# PIC32ETH_Ethernet.net
KiCad netlist of a schematic drawn in Altium Designer
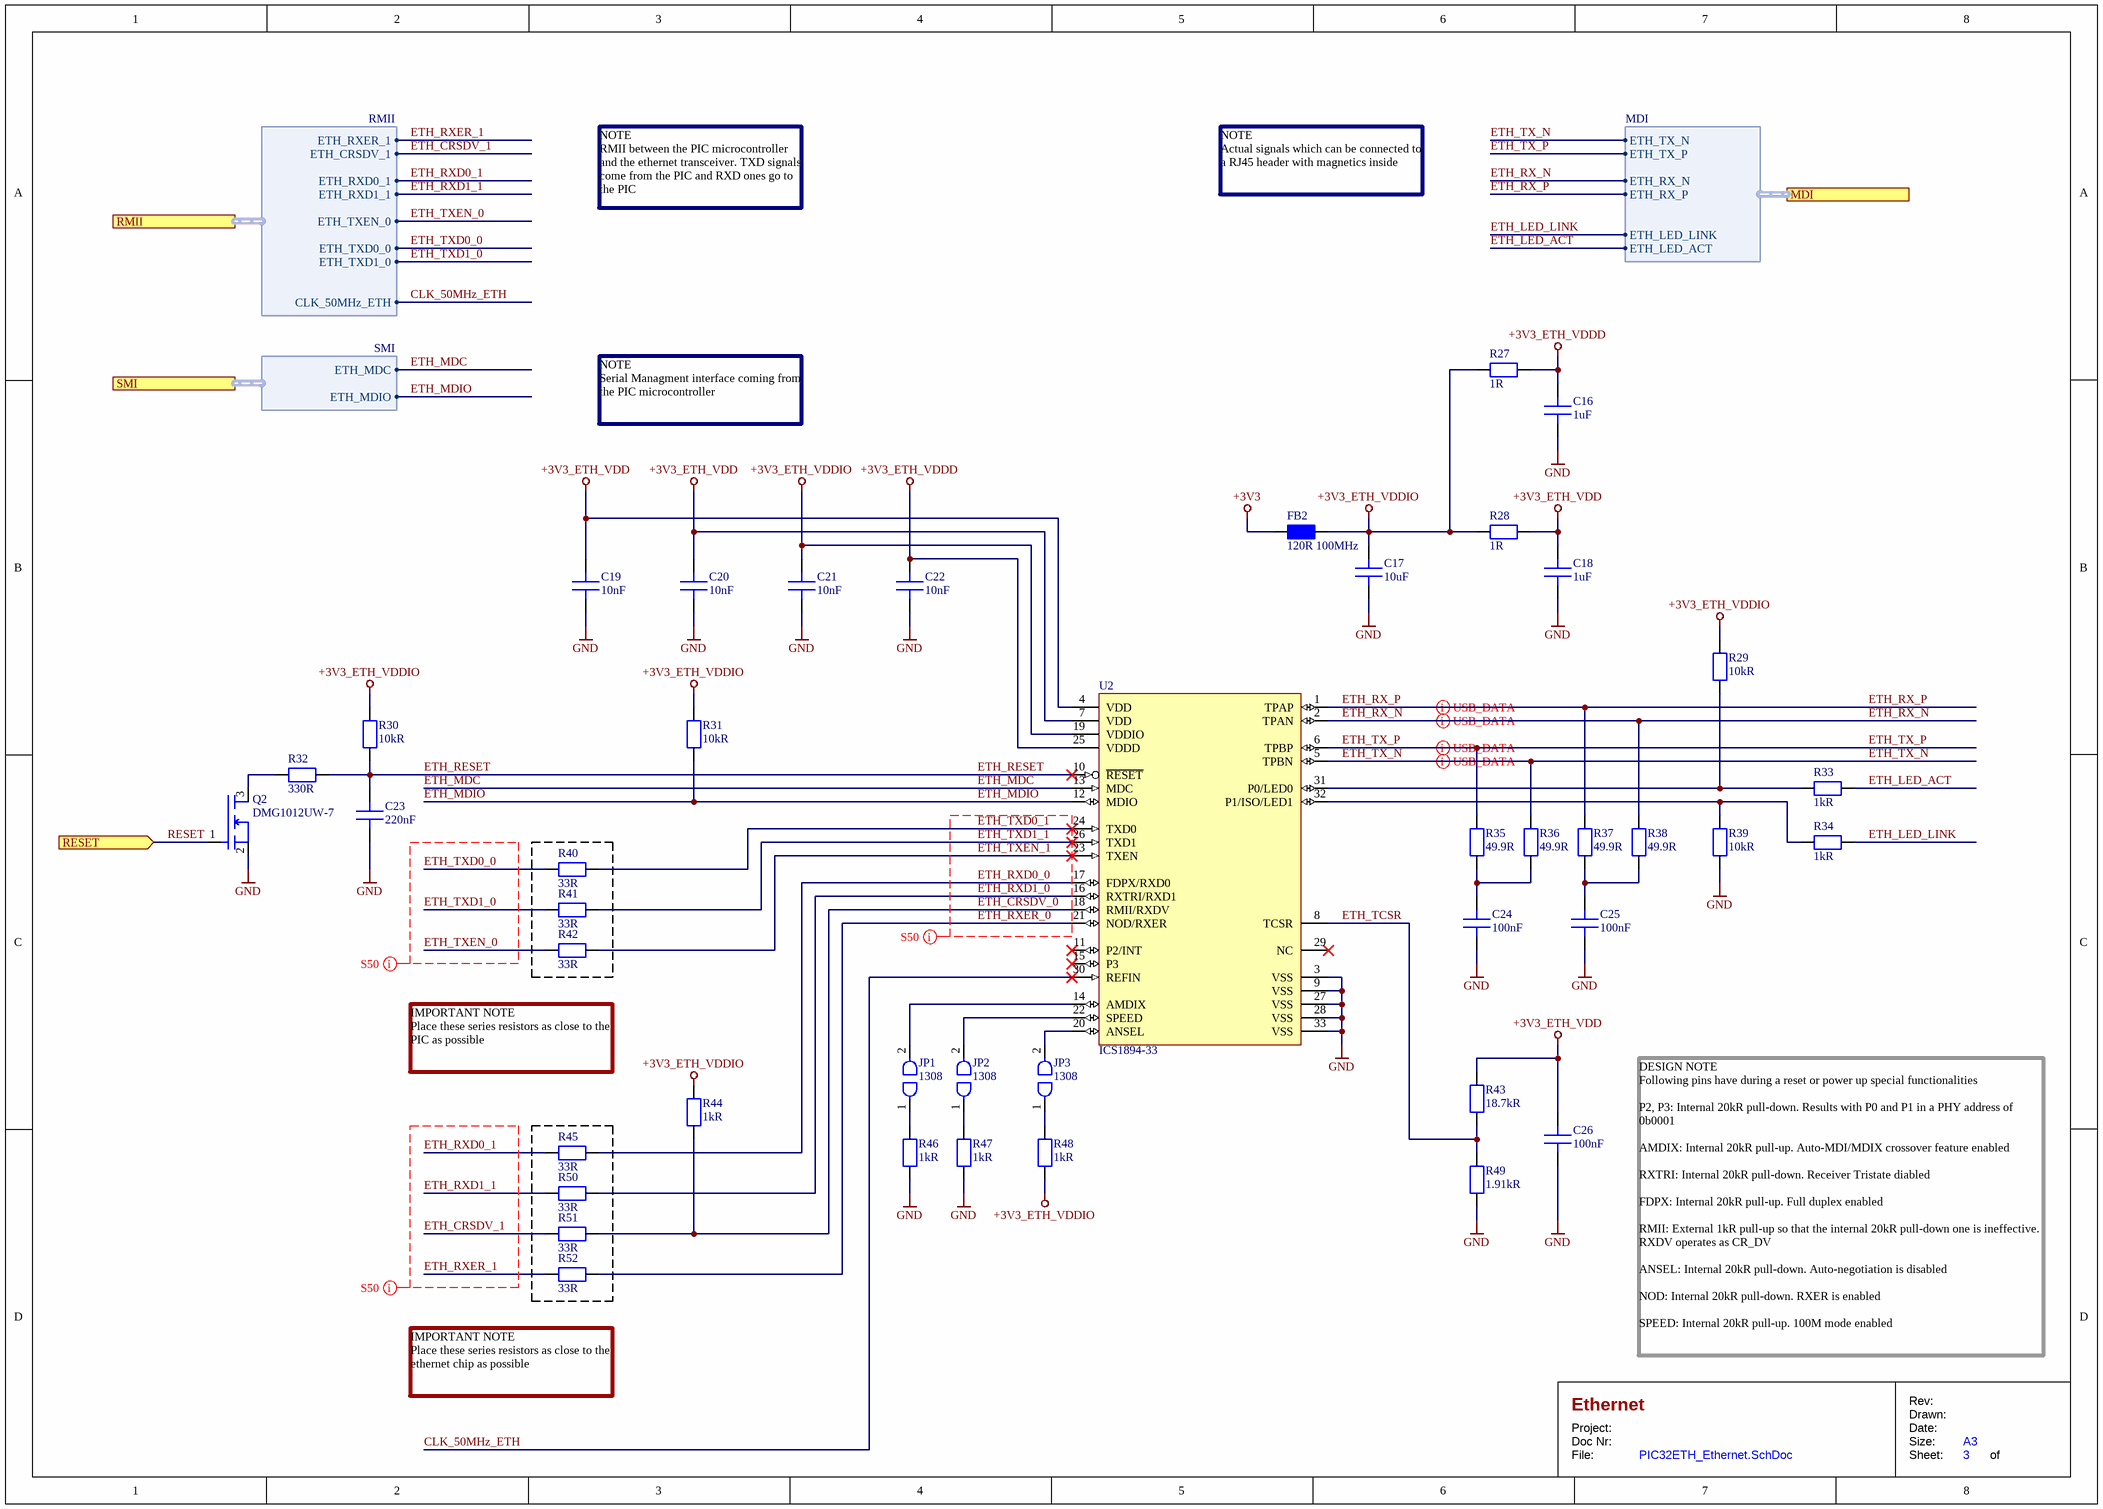
[diagram p0: PIC32ETH_Ethernet.SchDoc]

(export (version "E")
  (design (tool "Eeschema 10.0.6"))
  (components
    (comp (ref "C16")
      (value "1uF")
      (footprint "C_CHIP2012N")
      (description "C CERAMIC 1uF 50V 10% 2012")
      (fields (field (name "MANUFACTURER") "Kemet") (field (name "PART NUMBER") "C0805C105K5RACTU"))
      (libsource (lib "PIC32ETH") (part "C_C0805C105K5RACTU"))
    )
    (comp (ref "C17")
      (value "10uF")
      (footprint "C_CHIP3216N")
      (description "C CERAMIC 10uF 25V 10% 3216")
      (fields (field (name "PART NUMBER") "C1206C106K3RACTU") (field (name "MANUFACTURER") "Kemet"))
      (libsource (lib "PIC32ETH") (part "C_C1206C106K3RACTU"))
    )
    (comp (ref "C18")
      (value "1uF")
      (footprint "C_CHIP2012N")
      (description "C CERAMIC 1uF 50V 10% 2012")
      (fields (field (name "MANUFACTURER") "Kemet") (field (name "PART NUMBER") "C0805C105K5RACTU"))
      (libsource (lib "PIC32ETH") (part "C_C0805C105K5RACTU"))
    )
    (comp (ref "C19")
      (value "10nF")
      (footprint "C_CHIP2012N")
      (description "C CERAMIC 10nF 50V 10% 2012")
      (fields (field (name "MANUFACTURER") "Kemet") (field (name "PART NUMBER") "C0805C103K5RACTU"))
      (libsource (lib "PIC32ETH") (part "C_C0805C103K5RACTU"))
    )
    (comp (ref "C20")
      (value "10nF")
      (footprint "C_CHIP2012N")
      (description "C CERAMIC 10nF 50V 10% 2012")
      (fields (field (name "MANUFACTURER") "Kemet") (field (name "PART NUMBER") "C0805C103K5RACTU"))
      (libsource (lib "PIC32ETH") (part "C_C0805C103K5RACTU"))
    )
    (comp (ref "C21")
      (value "10nF")
      (footprint "C_CHIP2012N")
      (description "C CERAMIC 10nF 50V 10% 2012")
      (fields (field (name "MANUFACTURER") "Kemet") (field (name "PART NUMBER") "C0805C103K5RACTU"))
      (libsource (lib "PIC32ETH") (part "C_C0805C103K5RACTU"))
    )
    (comp (ref "C22")
      (value "10nF")
      (footprint "C_CHIP2012N")
      (description "C CERAMIC 10nF 50V 10% 2012")
      (fields (field (name "MANUFACTURER") "Kemet") (field (name "PART NUMBER") "C0805C103K5RACTU"))
      (libsource (lib "PIC32ETH") (part "C_C0805C103K5RACTU"))
    )
    (comp (ref "C23")
      (value "220nF")
      (footprint "C_CHIP2012N")
      (description "C CERAMIC 220nF 50V 10% 2012")
      (fields (field (name "MANUFACTURER") "Kemet") (field (name "PART NUMBER") "C0805C224K5RACTU"))
      (libsource (lib "PIC32ETH") (part "C_C0805C224K5RACTU"))
    )
    (comp (ref "C24")
      (value "100nF")
      (footprint "C_CHIP2012N")
      (description "C CERAMIC 100nF 50V 10% 2012")
      (fields (field (name "MANUFACTURER") "Kemet") (field (name "PART NUMBER") "C0805C104K5RACTU"))
      (libsource (lib "PIC32ETH") (part "C_C0805C104K5RACTU"))
    )
    (comp (ref "C25")
      (value "100nF")
      (footprint "C_CHIP2012N")
      (description "C CERAMIC 100nF 50V 10% 2012")
      (fields (field (name "MANUFACTURER") "Kemet") (field (name "PART NUMBER") "C0805C104K5RACTU"))
      (libsource (lib "PIC32ETH") (part "C_C0805C104K5RACTU"))
    )
    (comp (ref "C26")
      (value "100nF")
      (footprint "C_CHIP2012N")
      (description "C CERAMIC 100nF 50V 10% 2012")
      (fields (field (name "MANUFACTURER") "Kemet") (field (name "PART NUMBER") "C0805C104K5RACTU"))
      (libsource (lib "PIC32ETH") (part "C_C0805C104K5RACTU"))
    )
    (comp (ref "FB2")
      (value "120R 100MHz")
      (footprint "FB_CHIP3216N")
      (description "FB 120R 100MHz 6A 3216")
      (fields
        (field (name "MANUFACTURER") "Murata Electronics")
        (field (name "PART NUMBER") "BLM31KN121SN1L")
      )
      (libsource (lib "PIC32ETH") (part "FB_BLM31KN121SN1L"))
    )
    (comp (ref "JP1")
      (value "1308")
      (footprint "JP_SOLDER-2POS-1308")
      (description "JP SOLDER 2POS 1308")
      (fields (field (name "MANUFACTURER") "n/a"))
      (libsource (lib "PIC32ETH") (part "JP_SOLDER-2POS-1308"))
    )
    (comp (ref "JP2")
      (value "1308")
      (footprint "JP_SOLDER-2POS-1308")
      (description "JP SOLDER 2POS 1308")
      (fields (field (name "MANUFACTURER") "n/a"))
      (libsource (lib "PIC32ETH") (part "JP_SOLDER-2POS-1308"))
    )
    (comp (ref "JP3")
      (value "1308")
      (footprint "JP_SOLDER-2POS-1308")
      (description "JP SOLDER 2POS 1308")
      (fields (field (name "MANUFACTURER") "n/a"))
      (libsource (lib "PIC32ETH") (part "JP_SOLDER-2POS-1308"))
    )
    (comp (ref "Q2")
      (value "DMG1012UW-7")
      (footprint "Q_SOT65P210X100-3N")
      (description "Q MOSFET N-CH 20V 1A SOT-323")
      (fields (field (name "MANUFACTURER") "Diodes Incorporated") (field (name "POWER") "290mW"))
      (libsource (lib "PIC32ETH") (part "Q_DMG1012UW-7"))
    )
    (comp (ref "R27")
      (value "1R")
      (footprint "R_CHIP2012N")
      (description "R SMT 1R 1% 125mW 2012")
      (fields
        (field (name "MANUFACTURER") "Stackpole Electronics Inc")
        (field (name "PART NUMBER") "RMCF0805FT1R00")
      )
      (libsource (lib "PIC32ETH") (part "R_RMCF0805FT1R00"))
    )
    (comp (ref "R28")
      (value "1R")
      (footprint "R_CHIP2012N")
      (description "R SMT 1R 1% 125mW 2012")
      (fields
        (field (name "MANUFACTURER") "Stackpole Electronics Inc")
        (field (name "PART NUMBER") "RMCF0805FT1R00")
      )
      (libsource (lib "PIC32ETH") (part "R_RMCF0805FT1R00"))
    )
    (comp (ref "R29")
      (value "10kR")
      (footprint "R_CHIP2012N")
      (description "R SMT 10kR 1% 125mW 2012")
      (fields
        (field (name "MANUFACTURER") "Stackpole Electronics Inc")
        (field (name "PART NUMBER") "RMCF0805FT10K0")
      )
      (libsource (lib "PIC32ETH") (part "R_RMCF0805FT10K0"))
    )
    (comp (ref "R30")
      (value "10kR")
      (footprint "R_CHIP2012N")
      (description "R SMT 10kR 1% 125mW 2012")
      (fields
        (field (name "MANUFACTURER") "Stackpole Electronics Inc")
        (field (name "PART NUMBER") "RMCF0805FT10K0")
      )
      (libsource (lib "PIC32ETH") (part "R_RMCF0805FT10K0"))
    )
    (comp (ref "R31")
      (value "10kR")
      (footprint "R_CHIP2012N")
      (description "R SMT 10kR 1% 125mW 2012")
      (fields
        (field (name "MANUFACTURER") "Stackpole Electronics Inc")
        (field (name "PART NUMBER") "RMCF0805FT10K0")
      )
      (libsource (lib "PIC32ETH") (part "R_RMCF0805FT10K0"))
    )
    (comp (ref "R32")
      (value "330R")
      (footprint "R_CHIP2012N")
      (description "R SMT 330R 1% 125mW 2012")
      (fields
        (field (name "MANUFACTURER") "Stackpole Electronics Inc")
        (field (name "PART NUMBER") "RMCF0805FT330R")
      )
      (libsource (lib "PIC32ETH") (part "R_RMCF0805FT330R"))
    )
    (comp (ref "R33")
      (value "1kR")
      (footprint "R_CHIP2012N")
      (description "R SMT 1kR 1% 125mW 2012")
      (fields
        (field (name "MANUFACTURER") "Stackpole Electronics Inc")
        (field (name "PART NUMBER") "RMCF0805FT1K00")
      )
      (libsource (lib "PIC32ETH") (part "R_RMCF0805FT1K00"))
    )
    (comp (ref "R34")
      (value "1kR")
      (footprint "R_CHIP2012N")
      (description "R SMT 1kR 1% 125mW 2012")
      (fields
        (field (name "MANUFACTURER") "Stackpole Electronics Inc")
        (field (name "PART NUMBER") "RMCF0805FT1K00")
      )
      (libsource (lib "PIC32ETH") (part "R_RMCF0805FT1K00"))
    )
    (comp (ref "R35")
      (value "49.9R")
      (footprint "R_CHIP2012N")
      (description "R SMT 49.9R 1% 125mW 2012")
      (fields
        (field (name "MANUFACTURER") "Stackpole Electronics Inc")
        (field (name "PART NUMBER") "RMCF0805FT49R9")
      )
      (libsource (lib "PIC32ETH") (part "R_RMCF0805FT49R9"))
    )
    (comp (ref "R36")
      (value "49.9R")
      (footprint "R_CHIP2012N")
      (description "R SMT 49.9R 1% 125mW 2012")
      (fields
        (field (name "MANUFACTURER") "Stackpole Electronics Inc")
        (field (name "PART NUMBER") "RMCF0805FT49R9")
      )
      (libsource (lib "PIC32ETH") (part "R_RMCF0805FT49R9"))
    )
    (comp (ref "R37")
      (value "49.9R")
      (footprint "R_CHIP2012N")
      (description "R SMT 49.9R 1% 125mW 2012")
      (fields
        (field (name "MANUFACTURER") "Stackpole Electronics Inc")
        (field (name "PART NUMBER") "RMCF0805FT49R9")
      )
      (libsource (lib "PIC32ETH") (part "R_RMCF0805FT49R9"))
    )
    (comp (ref "R38")
      (value "49.9R")
      (footprint "R_CHIP2012N")
      (description "R SMT 49.9R 1% 125mW 2012")
      (fields
        (field (name "MANUFACTURER") "Stackpole Electronics Inc")
        (field (name "PART NUMBER") "RMCF0805FT49R9")
      )
      (libsource (lib "PIC32ETH") (part "R_RMCF0805FT49R9"))
    )
    (comp (ref "R39")
      (value "10kR")
      (footprint "R_CHIP2012N")
      (description "R SMT 10kR 1% 125mW 2012")
      (fields
        (field (name "MANUFACTURER") "Stackpole Electronics Inc")
        (field (name "PART NUMBER") "RMCF0805FT10K0")
      )
      (libsource (lib "PIC32ETH") (part "R_RMCF0805FT10K0"))
    )
    (comp (ref "R40")
      (value "33R")
      (footprint "R_CHIP2012N")
      (description "R SMT 33R 1% 125mW 2012")
      (fields
        (field (name "MANUFACTURER") "Stackpole Electronics Inc")
        (field (name "PART NUMBER") "RMCF0805FT33R0")
      )
      (libsource (lib "PIC32ETH") (part "R_RMCF0805FT33R0"))
    )
    (comp (ref "R41")
      (value "33R")
      (footprint "R_CHIP2012N")
      (description "R SMT 33R 1% 125mW 2012")
      (fields
        (field (name "MANUFACTURER") "Stackpole Electronics Inc")
        (field (name "PART NUMBER") "RMCF0805FT33R0")
      )
      (libsource (lib "PIC32ETH") (part "R_RMCF0805FT33R0"))
    )
    (comp (ref "R42")
      (value "33R")
      (footprint "R_CHIP2012N")
      (description "R SMT 33R 1% 125mW 2012")
      (fields
        (field (name "MANUFACTURER") "Stackpole Electronics Inc")
        (field (name "PART NUMBER") "RMCF0805FT33R0")
      )
      (libsource (lib "PIC32ETH") (part "R_RMCF0805FT33R0"))
    )
    (comp (ref "R43")
      (value "18.7kR")
      (footprint "R_CHIP2012N")
      (description "R SMT 18.7kR 1% 125mW 2012")
      (fields
        (field (name "MANUFACTURER") "Stackpole Electronics Inc")
        (field (name "PART NUMBER") "RMCF0805FT18K7")
      )
      (libsource (lib "PIC32ETH") (part "R_RMCF0805FT18K7"))
    )
    (comp (ref "R44")
      (value "1kR")
      (footprint "R_CHIP2012N")
      (description "R SMT 1kR 1% 125mW 2012")
      (fields
        (field (name "MANUFACTURER") "Stackpole Electronics Inc")
        (field (name "PART NUMBER") "RMCF0805FT1K00")
      )
      (libsource (lib "PIC32ETH") (part "R_RMCF0805FT1K00"))
    )
    (comp (ref "R45")
      (value "33R")
      (footprint "R_CHIP2012N")
      (description "R SMT 33R 1% 125mW 2012")
      (fields
        (field (name "MANUFACTURER") "Stackpole Electronics Inc")
        (field (name "PART NUMBER") "RMCF0805FT33R0")
      )
      (libsource (lib "PIC32ETH") (part "R_RMCF0805FT33R0"))
    )
    (comp (ref "R46")
      (value "1kR")
      (footprint "R_CHIP2012N")
      (description "R SMT 1kR 1% 125mW 2012")
      (fields
        (field (name "MANUFACTURER") "Stackpole Electronics Inc")
        (field (name "PART NUMBER") "RMCF0805FT1K00")
      )
      (libsource (lib "PIC32ETH") (part "R_RMCF0805FT1K00"))
    )
    (comp (ref "R47")
      (value "1kR")
      (footprint "R_CHIP2012N")
      (description "R SMT 1kR 1% 125mW 2012")
      (fields
        (field (name "MANUFACTURER") "Stackpole Electronics Inc")
        (field (name "PART NUMBER") "RMCF0805FT1K00")
      )
      (libsource (lib "PIC32ETH") (part "R_RMCF0805FT1K00"))
    )
    (comp (ref "R48")
      (value "1kR")
      (footprint "R_CHIP2012N")
      (description "R SMT 1kR 1% 125mW 2012")
      (fields
        (field (name "MANUFACTURER") "Stackpole Electronics Inc")
        (field (name "PART NUMBER") "RMCF0805FT1K00")
      )
      (libsource (lib "PIC32ETH") (part "R_RMCF0805FT1K00"))
    )
    (comp (ref "R49")
      (value "1.91kR")
      (footprint "R_CHIP2012N")
      (description "R SMT 1.91kR 1% 125mW 2012")
      (fields
        (field (name "MANUFACTURER") "Stackpole Electronics Inc")
        (field (name "PART NUMBER") "RMCF0805FT1K91")
      )
      (libsource (lib "PIC32ETH") (part "R_RMCF0805FT1K91"))
    )
    (comp (ref "R50")
      (value "33R")
      (footprint "R_CHIP2012N")
      (description "R SMT 33R 1% 125mW 2012")
      (fields
        (field (name "MANUFACTURER") "Stackpole Electronics Inc")
        (field (name "PART NUMBER") "RMCF0805FT33R0")
      )
      (libsource (lib "PIC32ETH") (part "R_RMCF0805FT33R0"))
    )
    (comp (ref "R51")
      (value "33R")
      (footprint "R_CHIP2012N")
      (description "R SMT 33R 1% 125mW 2012")
      (fields
        (field (name "MANUFACTURER") "Stackpole Electronics Inc")
        (field (name "PART NUMBER") "RMCF0805FT33R0")
      )
      (libsource (lib "PIC32ETH") (part "R_RMCF0805FT33R0"))
    )
    (comp (ref "R52")
      (value "33R")
      (footprint "R_CHIP2012N")
      (description "R SMT 33R 1% 125mW 2012")
      (fields
        (field (name "MANUFACTURER") "Stackpole Electronics Inc")
        (field (name "PART NUMBER") "RMCF0805FT33R0")
      )
      (libsource (lib "PIC32ETH") (part "R_RMCF0805FT33R0"))
    )
    (comp (ref "U2")
      (value "ICS1894-33")
      (footprint "U_QFN50P500X500X100-HS-33N")
      (description "U TRANSCEIVER RMII-ETHERNET 32-QFN")
      (fields (field (name "MANUFACTURER") "Renesas"))
      (libsource (lib "PIC32ETH") (part "U_ICS1894-33"))
    )
  )
  (nets
    (net (code "4") (name "+3V3") (class "Default")
      (node (ref "FB2") (pin "1") (pinfunction "1_1") (pintype "passive"))
    )
    (net (code "5") (name "+3V3_ETH_VDD") (class "Default")
      (node (ref "C18") (pin "1") (pinfunction "1_1") (pintype "passive"))
      (node (ref "C19") (pin "2") (pinfunction "2_2") (pintype "passive"))
      (node (ref "C20") (pin "2") (pinfunction "2_2") (pintype "passive"))
      (node (ref "C26") (pin "1") (pinfunction "1_1") (pintype "passive"))
      (node (ref "R28") (pin "2") (pinfunction "2_2") (pintype "passive"))
      (node (ref "R43") (pin "2") (pinfunction "2_2") (pintype "passive"))
      (node (ref "U2") (pin "4") (pinfunction "VDD_4") (pintype "power_in"))
      (node (ref "U2") (pin "7") (pinfunction "VDD_7") (pintype "power_in"))
    )
    (net (code "6") (name "+3V3_ETH_VDDD") (class "Default")
      (node (ref "C16") (pin "1") (pinfunction "1_1") (pintype "passive"))
      (node (ref "C22") (pin "2") (pinfunction "2_2") (pintype "passive"))
      (node (ref "R27") (pin "2") (pinfunction "2_2") (pintype "passive"))
      (node (ref "U2") (pin "25") (pinfunction "VDDD_25") (pintype "power_in"))
    )
    (net (code "7") (name "+3V3_ETH_VDDIO") (class "Default")
      (node (ref "C17") (pin "2") (pinfunction "2_2") (pintype "passive"))
      (node (ref "C21") (pin "2") (pinfunction "2_2") (pintype "passive"))
      (node (ref "FB2") (pin "2") (pinfunction "2_2") (pintype "passive"))
      (node (ref "R27") (pin "1") (pinfunction "1_1") (pintype "passive"))
      (node (ref "R28") (pin "1") (pinfunction "1_1") (pintype "passive"))
      (node (ref "R29") (pin "1") (pinfunction "1_1") (pintype "passive"))
      (node (ref "R30") (pin "2") (pinfunction "2_2") (pintype "passive"))
      (node (ref "R31") (pin "2") (pinfunction "2_2") (pintype "passive"))
      (node (ref "R44") (pin "2") (pinfunction "2_2") (pintype "passive"))
      (node (ref "R48") (pin "1") (pinfunction "1_1") (pintype "passive"))
      (node (ref "U2") (pin "19") (pinfunction "VDDIO_19") (pintype "power_in"))
    )
    (net (code "8") (name "/CLK_50MHz_ETH") (class "Default")
      (node (ref "U2") (pin "30") (pinfunction "REFIN_30") (pintype "input+no_connect"))
    )
    (net (code "9") (name "/ETH_CRSDV_0") (class "Default")
      (node (ref "R44") (pin "1") (pinfunction "1_1") (pintype "passive"))
      (node (ref "R51") (pin "2") (pinfunction "2_2") (pintype "passive"))
      (node (ref "U2") (pin "18") (pinfunction "RMII/RXDV_18") (pintype "bidirectional"))
    )
    (net (code "10") (name "/ETH_CRSDV_1") (class "Default")
      (node (ref "R51") (pin "1") (pinfunction "1_1") (pintype "passive"))
    )
    (net (code "11") (name "/ETH_LED_ACT") (class "Default")
      (node (ref "R33") (pin "1") (pinfunction "1_1") (pintype "passive"))
    )
    (net (code "12") (name "/ETH_LED_LINK") (class "Default")
      (node (ref "R34") (pin "1") (pinfunction "1_1") (pintype "passive"))
    )
    (net (code "13") (name "/ETH_MDC") (class "Default")
      (node (ref "U2") (pin "13") (pinfunction "MDC_13") (pintype "input"))
    )
    (net (code "14") (name "/ETH_MDIO") (class "Default")
      (node (ref "R31") (pin "1") (pinfunction "1_1") (pintype "passive"))
      (node (ref "U2") (pin "12") (pinfunction "MDIO_12") (pintype "bidirectional"))
    )
    (net (code "15") (name "/ETH_RESET") (class "Default")
      (node (ref "C23") (pin "2") (pinfunction "2_2") (pintype "passive"))
      (node (ref "R30") (pin "1") (pinfunction "1_1") (pintype "passive"))
      (node (ref "R32") (pin "2") (pinfunction "2_2") (pintype "passive"))
      (node (ref "U2") (pin "10") (pinfunction "~{RESET}_10") (pintype "input"))
    )
    (net (code "16") (name "/ETH_RXD0_0") (class "Default")
      (node (ref "R45") (pin "2") (pinfunction "2_2") (pintype "passive"))
      (node (ref "U2") (pin "17") (pinfunction "FDPX/RXD0_17") (pintype "bidirectional"))
    )
    (net (code "17") (name "/ETH_RXD0_1") (class "Default")
      (node (ref "R45") (pin "1") (pinfunction "1_1") (pintype "passive"))
    )
    (net (code "18") (name "/ETH_RXD1_0") (class "Default")
      (node (ref "R50") (pin "2") (pinfunction "2_2") (pintype "passive"))
      (node (ref "U2") (pin "16") (pinfunction "RXTRI/RXD1_16") (pintype "bidirectional"))
    )
    (net (code "19") (name "/ETH_RXD1_1") (class "Default")
      (node (ref "R50") (pin "1") (pinfunction "1_1") (pintype "passive"))
    )
    (net (code "20") (name "/ETH_RXER_0") (class "Default")
      (node (ref "R52") (pin "2") (pinfunction "2_2") (pintype "passive"))
      (node (ref "U2") (pin "21") (pinfunction "NOD/RXER_21") (pintype "bidirectional"))
    )
    (net (code "21") (name "/ETH_RXER_1") (class "Default")
      (node (ref "R52") (pin "1") (pinfunction "1_1") (pintype "passive"))
    )
    (net (code "22") (name "/ETH_RX_N") (class "Default")
      (node (ref "R38") (pin "2") (pinfunction "2_2") (pintype "passive"))
      (node (ref "U2") (pin "2") (pinfunction "TPAN_2") (pintype "bidirectional"))
    )
    (net (code "23") (name "/ETH_RX_P") (class "Default")
      (node (ref "R37") (pin "2") (pinfunction "2_2") (pintype "passive"))
      (node (ref "U2") (pin "1") (pinfunction "TPAP_1") (pintype "bidirectional"))
    )
    (net (code "24") (name "/ETH_TCSR") (class "Default")
      (node (ref "R43") (pin "1") (pinfunction "1_1") (pintype "passive"))
      (node (ref "R49") (pin "2") (pinfunction "2_2") (pintype "passive"))
      (node (ref "U2") (pin "8") (pinfunction "TCSR_8") (pintype "passive"))
    )
    (net (code "25") (name "/ETH_TXD0_0") (class "Default")
      (node (ref "R40") (pin "1") (pinfunction "1_1") (pintype "passive"))
    )
    (net (code "26") (name "/ETH_TXD0_1") (class "Default")
      (node (ref "R40") (pin "2") (pinfunction "2_2") (pintype "passive"))
      (node (ref "U2") (pin "24") (pinfunction "TXD0_24") (pintype "input"))
    )
    (net (code "27") (name "/ETH_TXD1_0") (class "Default")
      (node (ref "R41") (pin "1") (pinfunction "1_1") (pintype "passive"))
    )
    (net (code "28") (name "/ETH_TXD1_1") (class "Default")
      (node (ref "R41") (pin "2") (pinfunction "2_2") (pintype "passive"))
      (node (ref "U2") (pin "26") (pinfunction "TXD1_26") (pintype "input"))
    )
    (net (code "29") (name "/ETH_TXEN_0") (class "Default")
      (node (ref "R42") (pin "1") (pinfunction "1_1") (pintype "passive"))
    )
    (net (code "30") (name "/ETH_TXEN_1") (class "Default")
      (node (ref "R42") (pin "2") (pinfunction "2_2") (pintype "passive"))
      (node (ref "U2") (pin "23") (pinfunction "TXEN_23") (pintype "input"))
    )
    (net (code "31") (name "/ETH_TX_N") (class "Default")
      (node (ref "R36") (pin "2") (pinfunction "2_2") (pintype "passive"))
      (node (ref "U2") (pin "5") (pinfunction "TPBN_5") (pintype "bidirectional"))
    )
    (net (code "32") (name "/ETH_TX_P") (class "Default")
      (node (ref "R35") (pin "2") (pinfunction "2_2") (pintype "passive"))
      (node (ref "U2") (pin "6") (pinfunction "TPBP_6") (pintype "bidirectional"))
    )
    (net (code "33") (name "/RESET") (class "Default")
      (node (ref "Q2") (pin "1") (pinfunction "G_1") (pintype "passive"))
    )
    (net (code "37") (name "GND") (class "Default")
      (node (ref "C16") (pin "2") (pinfunction "2_2") (pintype "passive"))
      (node (ref "C17") (pin "1") (pinfunction "1_1") (pintype "passive"))
      (node (ref "C18") (pin "2") (pinfunction "2_2") (pintype "passive"))
      (node (ref "C19") (pin "1") (pinfunction "1_1") (pintype "passive"))
      (node (ref "C20") (pin "1") (pinfunction "1_1") (pintype "passive"))
      (node (ref "C21") (pin "1") (pinfunction "1_1") (pintype "passive"))
      (node (ref "C22") (pin "1") (pinfunction "1_1") (pintype "passive"))
      (node (ref "C23") (pin "1") (pinfunction "1_1") (pintype "passive"))
      (node (ref "C24") (pin "2") (pinfunction "2_2") (pintype "passive"))
      (node (ref "C25") (pin "2") (pinfunction "2_2") (pintype "passive"))
      (node (ref "C26") (pin "2") (pinfunction "2_2") (pintype "passive"))
      (node (ref "Q2") (pin "2") (pinfunction "S_2") (pintype "passive"))
      (node (ref "R39") (pin "1") (pinfunction "1_1") (pintype "passive"))
      (node (ref "R46") (pin "1") (pinfunction "1_1") (pintype "passive"))
      (node (ref "R47") (pin "1") (pinfunction "1_1") (pintype "passive"))
      (node (ref "R49") (pin "1") (pinfunction "1_1") (pintype "passive"))
      (node (ref "U2") (pin "27") (pinfunction "VSS_27") (pintype "power_in"))
      (node (ref "U2") (pin "28") (pinfunction "VSS_28") (pintype "power_in"))
      (node (ref "U2") (pin "3") (pinfunction "VSS_3") (pintype "power_in"))
      (node (ref "U2") (pin "33") (pinfunction "VSS_33") (pintype "power_in"))
      (node (ref "U2") (pin "9") (pinfunction "VSS_9") (pintype "power_in"))
    )
    (net (code "38") (name "Net-(C24-Pad1)") (class "Default")
      (node (ref "C24") (pin "1") (pinfunction "1_1") (pintype "passive"))
      (node (ref "R35") (pin "1") (pinfunction "1_1") (pintype "passive"))
      (node (ref "R36") (pin "1") (pinfunction "1_1") (pintype "passive"))
    )
    (net (code "39") (name "Net-(C25-Pad1)") (class "Default")
      (node (ref "C25") (pin "1") (pinfunction "1_1") (pintype "passive"))
      (node (ref "R37") (pin "1") (pinfunction "1_1") (pintype "passive"))
      (node (ref "R38") (pin "1") (pinfunction "1_1") (pintype "passive"))
    )
    (net (code "40") (name "Net-(JP1-Pad1)") (class "Default")
      (node (ref "JP1") (pin "1") (pinfunction "1_1") (pintype "passive"))
      (node (ref "R46") (pin "2") (pinfunction "2_2") (pintype "passive"))
    )
    (net (code "41") (name "Net-(JP2-Pad1)") (class "Default")
      (node (ref "JP2") (pin "1") (pinfunction "1_1") (pintype "passive"))
      (node (ref "R47") (pin "2") (pinfunction "2_2") (pintype "passive"))
    )
    (net (code "42") (name "Net-(JP3-Pad1)") (class "Default")
      (node (ref "JP3") (pin "1") (pinfunction "1_1") (pintype "passive"))
      (node (ref "R48") (pin "2") (pinfunction "2_2") (pintype "passive"))
    )
    (net (code "43") (name "Net-(Q2-D)") (class "Default")
      (node (ref "Q2") (pin "3") (pinfunction "D_3") (pintype "passive"))
      (node (ref "R32") (pin "1") (pinfunction "1_1") (pintype "passive"))
    )
    (net (code "44") (name "Net-(U2-AMDIX)") (class "Default")
      (node (ref "JP1") (pin "2") (pinfunction "2_2") (pintype "passive"))
      (node (ref "U2") (pin "14") (pinfunction "AMDIX_14") (pintype "bidirectional"))
    )
    (net (code "45") (name "Net-(U2-ANSEL)") (class "Default")
      (node (ref "JP3") (pin "2") (pinfunction "2_2") (pintype "passive"))
      (node (ref "U2") (pin "20") (pinfunction "ANSEL_20") (pintype "bidirectional"))
    )
    (net (code "46") (name "Net-(U2-P0{slash}LED0)") (class "Default")
      (node (ref "R29") (pin "2") (pinfunction "2_2") (pintype "passive"))
      (node (ref "R33") (pin "2") (pinfunction "2_2") (pintype "passive"))
      (node (ref "U2") (pin "31") (pinfunction "P0/LED0_31") (pintype "bidirectional"))
    )
    (net (code "47") (name "Net-(U2-P1{slash}ISO{slash}LED1)") (class "Default")
      (node (ref "R34") (pin "2") (pinfunction "2_2") (pintype "passive"))
      (node (ref "R39") (pin "2") (pinfunction "2_2") (pintype "passive"))
      (node (ref "U2") (pin "32") (pinfunction "P1/ISO/LED1_32") (pintype "bidirectional"))
    )
    (net (code "48") (name "Net-(U2-SPEED)") (class "Default")
      (node (ref "JP2") (pin "2") (pinfunction "2_2") (pintype "passive"))
      (node (ref "U2") (pin "22") (pinfunction "SPEED_22") (pintype "bidirectional"))
    )
    (net (code "49") (name "unconnected-(U2-NC-Pad29)") (class "Default")
      (node (ref "U2") (pin "29") (pinfunction "NC_29") (pintype "passive+no_connect"))
    )
    (net (code "50") (name "unconnected-(U2-P2{slash}INT-Pad11)") (class "Default")
      (node (ref "U2") (pin "11") (pinfunction "P2/INT_11") (pintype "bidirectional+no_connect"))
    )
    (net (code "51") (name "unconnected-(U2-P3-Pad15)") (class "Default")
      (node (ref "U2") (pin "15") (pinfunction "P3_15") (pintype "bidirectional+no_connect"))
    )
  )
)
